# BrightButton.net
KiCad netlist of a schematic drawn in EAGLE
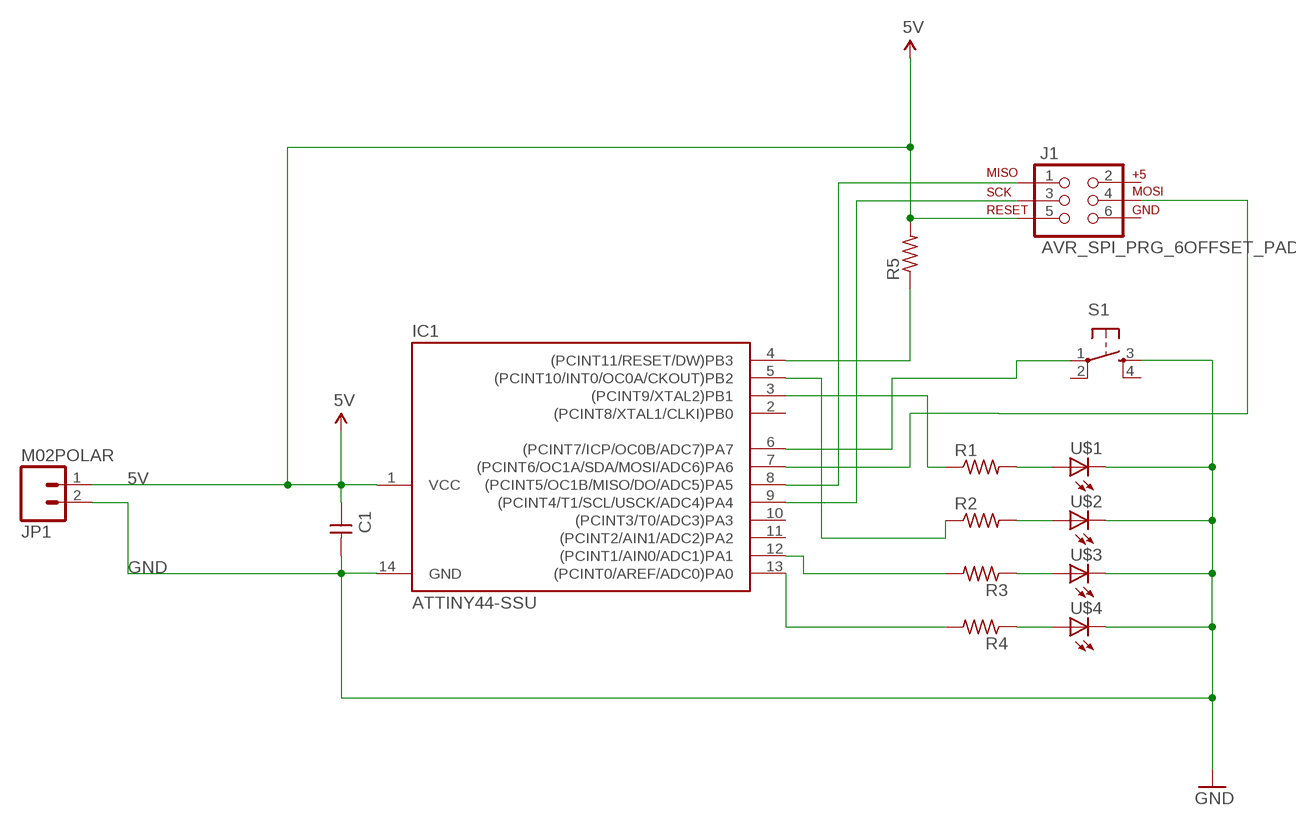
[diagram p0: schematic, sheet 1]

(export (version "E")
  (design (tool "Eeschema 10.0.6"))
  (components
    (comp (ref "C1")
      (value "UNPOLARIZED_CAPACITOR1206")
      (footprint "eagle-import:1206")
      (libsource (lib "eagle-import") (part "UNPOLARIZED_CAPACITOR1206"))
    )
    (comp (ref "IC1")
      (value "ATTINY44-SSU")
      (footprint "eagle-import:SOIC14")
      (libsource (lib "eagle-import") (part "ATTINY44-SSU"))
    )
    (comp (ref "J1")
      (value "AVR_SPI_PRG_6OFFSET_PADS")
      (footprint "eagle-import:2X3_OFFSET")
      (libsource (lib "eagle-import") (part "AVR_SPI_PRG_6OFFSET_PADS"))
    )
    (comp (ref "JP1")
      (value "M02POLAR")
      (footprint "eagle-import:MOLEX-1X2")
      (libsource (lib "eagle-import") (part "M02POLAR"))
    )
    (comp (ref "R1")
      (value "RESISTOR1206")
      (footprint "eagle-import:1206")
      (libsource (lib "eagle-import") (part "RESISTOR1206"))
    )
    (comp (ref "R2")
      (value "RESISTOR1206")
      (footprint "eagle-import:1206")
      (libsource (lib "eagle-import") (part "RESISTOR1206"))
    )
    (comp (ref "R3")
      (value "RESISTOR1206")
      (footprint "eagle-import:1206")
      (libsource (lib "eagle-import") (part "RESISTOR1206"))
    )
    (comp (ref "R4")
      (value "RESISTOR1206")
      (footprint "eagle-import:1206")
      (libsource (lib "eagle-import") (part "RESISTOR1206"))
    )
    (comp (ref "R5")
      (value "RESISTOR1206")
      (footprint "eagle-import:1206")
      (libsource (lib "eagle-import") (part "RESISTOR1206"))
    )
    (comp (ref "S1")
      (value "6MM_SWITCH6MM_SWITCH")
      (footprint "eagle-import:6MM_SWITCH")
      (libsource (lib "eagle-import") (part "6MM_SWITCH6MM_SWITCH"))
    )
    (comp (ref "U$1")
      (value "LED1206")
      (footprint "eagle-import:1206")
      (libsource (lib "eagle-import") (part "LED1206"))
    )
    (comp (ref "U$2")
      (value "LED1206")
      (footprint "eagle-import:1206")
      (libsource (lib "eagle-import") (part "LED1206"))
    )
    (comp (ref "U$3")
      (value "LED1206")
      (footprint "eagle-import:1206")
      (libsource (lib "eagle-import") (part "LED1206"))
    )
    (comp (ref "U$4")
      (value "LED1206")
      (footprint "eagle-import:1206")
      (libsource (lib "eagle-import") (part "LED1206"))
    )
  )
  (nets
    (net (code "1") (name "5V") (class "Default")
      (node (ref "C1") (pin "1") (pinfunction "1_1") (pintype "passive"))
      (node (ref "IC1") (pin "1") (pinfunction "VCC_1") (pintype "power_in"))
      (node (ref "J1") (pin "5") (pinfunction "5_5") (pintype "passive"))
      (node (ref "JP1") (pin "1") (pinfunction "1_1") (pintype "passive"))
      (node (ref "R5") (pin "2") (pinfunction "2_2") (pintype "passive"))
    )
    (net (code "2") (name "GND") (class "Default")
      (node (ref "C1") (pin "2") (pinfunction "2_2") (pintype "passive"))
      (node (ref "IC1") (pin "14") (pinfunction "GND_14") (pintype "power_in"))
      (node (ref "JP1") (pin "2") (pinfunction "2_2") (pintype "passive"))
      (node (ref "S1") (pin "3") (pinfunction "S_3") (pintype "passive"))
      (node (ref "U$1") (pin "2") (pinfunction "C_2") (pintype "passive"))
      (node (ref "U$2") (pin "2") (pinfunction "C_2") (pintype "passive"))
      (node (ref "U$3") (pin "2") (pinfunction "C_2") (pintype "passive"))
      (node (ref "U$4") (pin "2") (pinfunction "C_2") (pintype "passive"))
    )
    (net (code "3") (name "Net-(IC1-(PCINT0{slash}AREF{slash}ADC0)PA0)") (class "Default")
      (node (ref "IC1") (pin "13") (pinfunction "(PCINT0/AREF/ADC0)PA0_13") (pintype "bidirectional"))
      (node (ref "R4") (pin "2") (pinfunction "2_2") (pintype "passive"))
    )
    (net (code "4") (name "Net-(IC1-(PCINT1{slash}AIN0{slash}ADC1)PA1)") (class "Default")
      (node (ref "IC1") (pin "12") (pinfunction "(PCINT1/AIN0/ADC1)PA1_12") (pintype "bidirectional"))
      (node (ref "R3") (pin "2") (pinfunction "2_2") (pintype "passive"))
    )
    (net (code "5") (name "Net-(IC1-(PCINT4{slash}T1{slash}SCL{slash}USCK{slash}ADC4)PA4)") (class "Default")
      (node (ref "IC1") (pin "9") (pinfunction "(PCINT4/T1/SCL/USCK/ADC4)PA4_9") (pintype "bidirectional"))
      (node (ref "J1") (pin "3") (pinfunction "3_3") (pintype "passive"))
    )
    (net (code "6") (name "Net-(IC1-(PCINT5{slash}OC1B{slash}MISO{slash}DO{slash}ADC5)PA5)") (class "Default")
      (node (ref "IC1") (pin "8") (pinfunction "(PCINT5/OC1B/MISO/DO/ADC5)PA5_8") (pintype "bidirectional"))
      (node (ref "J1") (pin "1") (pinfunction "1_1") (pintype "passive"))
    )
    (net (code "7") (name "Net-(IC1-(PCINT6{slash}OC1A{slash}SDA{slash}MOSI{slash}ADC6)PA6)") (class "Default")
      (node (ref "IC1") (pin "7") (pinfunction "(PCINT6/OC1A/SDA/MOSI/ADC6)PA6_7") (pintype "bidirectional"))
      (node (ref "J1") (pin "4") (pinfunction "4_4") (pintype "passive"))
    )
    (net (code "8") (name "Net-(IC1-(PCINT7{slash}ICP{slash}OC0B{slash}ADC7)PA7)") (class "Default")
      (node (ref "IC1") (pin "6") (pinfunction "(PCINT7/ICP/OC0B/ADC7)PA7_6") (pintype "bidirectional"))
      (node (ref "S1") (pin "1") (pinfunction "P_1") (pintype "passive"))
    )
    (net (code "9") (name "Net-(IC1-(PCINT9{slash}XTAL2)PB1)") (class "Default")
      (node (ref "IC1") (pin "3") (pinfunction "(PCINT9/XTAL2)PB1_3") (pintype "bidirectional"))
      (node (ref "R1") (pin "1") (pinfunction "1_1") (pintype "passive"))
    )
    (net (code "10") (name "Net-(IC1-(PCINT10{slash}INT0{slash}OC0A{slash}CKOUT)PB2)") (class "Default")
      (node (ref "IC1") (pin "5") (pinfunction "(PCINT10/INT0/OC0A/CKOUT)PB2_5") (pintype "bidirectional"))
      (node (ref "R2") (pin "1") (pinfunction "1_1") (pintype "passive"))
    )
    (net (code "11") (name "Net-(IC1-(PCINT11{slash}RESET{slash}DW)PB3)") (class "Default")
      (node (ref "IC1") (pin "4") (pinfunction "(PCINT11/RESET/DW)PB3_4") (pintype "bidirectional"))
      (node (ref "R5") (pin "1") (pinfunction "1_1") (pintype "passive"))
    )
    (net (code "12") (name "Net-(U$1-A)") (class "Default")
      (node (ref "R1") (pin "2") (pinfunction "2_2") (pintype "passive"))
      (node (ref "U$1") (pin "1") (pinfunction "A_1") (pintype "passive"))
    )
    (net (code "13") (name "Net-(U$2-A)") (class "Default")
      (node (ref "R2") (pin "2") (pinfunction "2_2") (pintype "passive"))
      (node (ref "U$2") (pin "1") (pinfunction "A_1") (pintype "passive"))
    )
    (net (code "14") (name "Net-(U$3-A)") (class "Default")
      (node (ref "R3") (pin "1") (pinfunction "1_1") (pintype "passive"))
      (node (ref "U$3") (pin "1") (pinfunction "A_1") (pintype "passive"))
    )
    (net (code "15") (name "Net-(U$4-A)") (class "Default")
      (node (ref "R4") (pin "1") (pinfunction "1_1") (pintype "passive"))
      (node (ref "U$4") (pin "1") (pinfunction "A_1") (pintype "passive"))
    )
    (net (code "16") (name "unconnected-(IC1-(PCINT2{slash}AIN1{slash}ADC2)PA2-Pad11)") (class "Default")
      (node (ref "IC1") (pin "11") (pinfunction "(PCINT2/AIN1/ADC2)PA2_11") (pintype "bidirectional"))
    )
    (net (code "17") (name "unconnected-(IC1-(PCINT3{slash}T0{slash}ADC3)PA3-Pad10)") (class "Default")
      (node (ref "IC1") (pin "10") (pinfunction "(PCINT3/T0/ADC3)PA3_10") (pintype "bidirectional"))
    )
    (net (code "18") (name "unconnected-(IC1-(PCINT8{slash}XTAL1{slash}CLKI)PB0-Pad2)") (class "Default")
      (node (ref "IC1") (pin "2") (pinfunction "(PCINT8/XTAL1/CLKI)PB0_2") (pintype "bidirectional"))
    )
    (net (code "19") (name "unconnected-(J1-Pad2)") (class "Default")
      (node (ref "J1") (pin "2") (pinfunction "2_2") (pintype "passive"))
    )
    (net (code "20") (name "unconnected-(J1-Pad6)") (class "Default")
      (node (ref "J1") (pin "6") (pinfunction "6_6") (pintype "passive"))
    )
    (net (code "21") (name "unconnected-(S1-P1-Pad2)") (class "Default")
      (node (ref "S1") (pin "2") (pinfunction "P1_2") (pintype "passive"))
    )
    (net (code "22") (name "unconnected-(S1-S1-Pad4)") (class "Default")
      (node (ref "S1") (pin "4") (pinfunction "S1_4") (pintype "passive"))
    )
  )
)
